# LED_Keychain_rev2.net
KiCad netlist of a schematic drawn in EAGLE
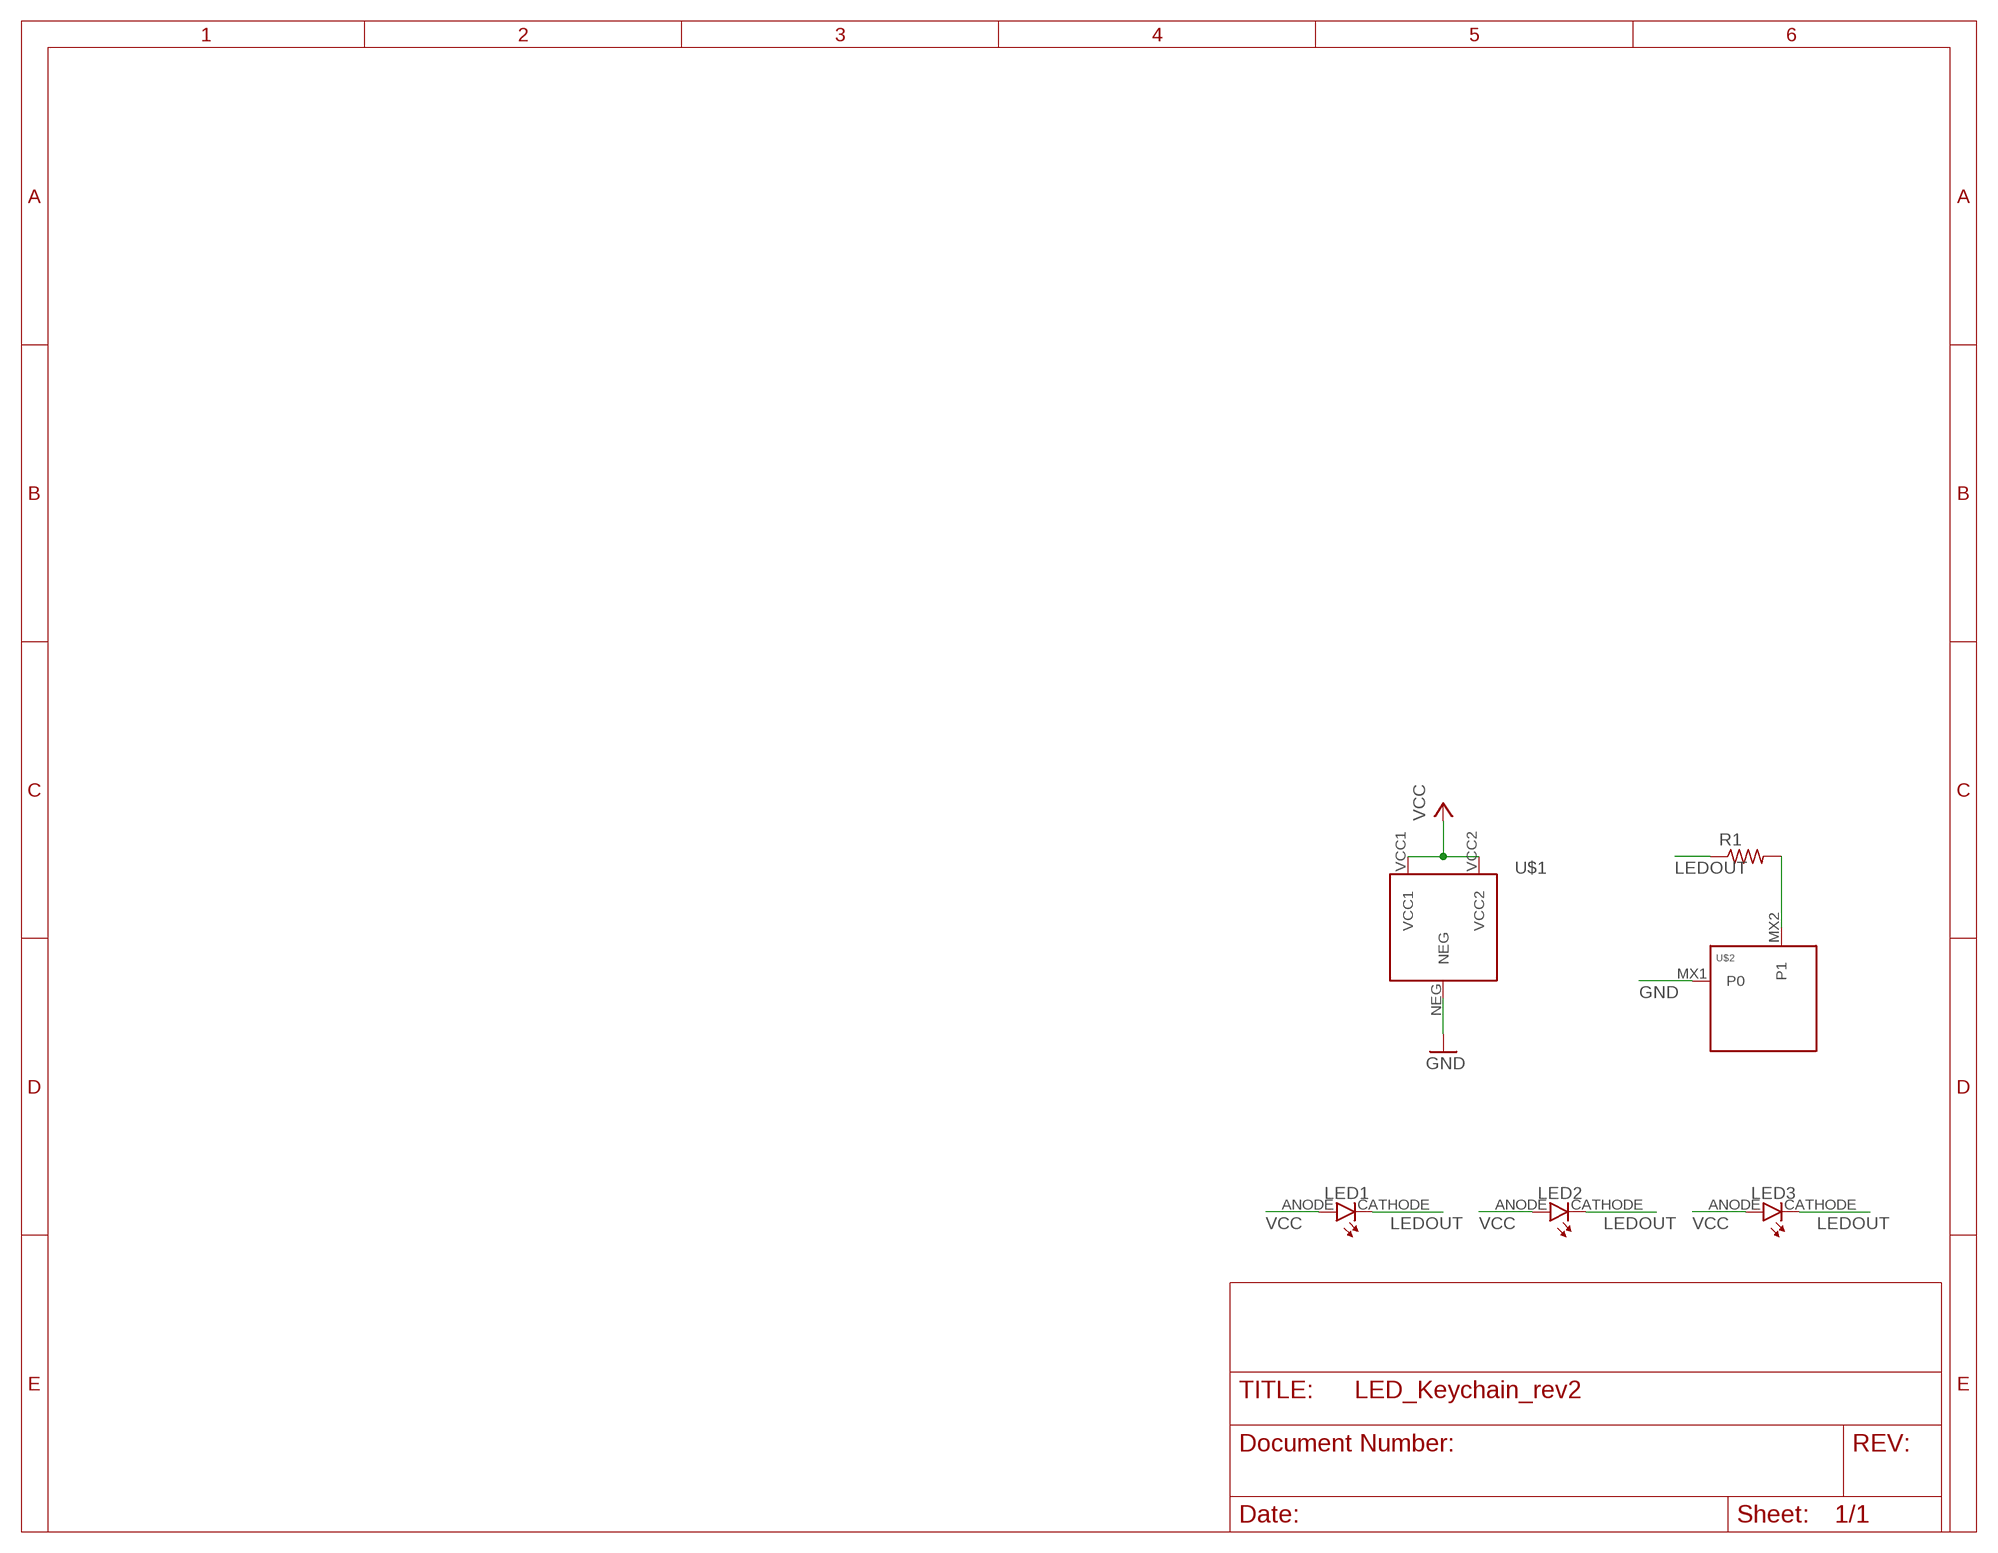
[diagram p0: schematic, sheet 1]

(export (version "E")
  (design (tool "Eeschema 10.0.6"))
  (components
    (comp (ref "LED1")
      (value "KINGBRIGHT-A1608")
      (footprint "eagle-import:KINGBRIGHT-0603")
      (libsource (lib "eagle-import") (part "KINGBRIGHT-A1608"))
    )
    (comp (ref "LED2")
      (value "KINGBRIGHT-A1608")
      (footprint "eagle-import:KINGBRIGHT-0603")
      (libsource (lib "eagle-import") (part "KINGBRIGHT-A1608"))
    )
    (comp (ref "LED3")
      (value "KINGBRIGHT-A1608")
      (footprint "eagle-import:KINGBRIGHT-0603")
      (libsource (lib "eagle-import") (part "KINGBRIGHT-A1608"))
    )
    (comp (ref "R1")
      (value "R-US_R0603")
      (footprint "eagle-import:R0603")
      (libsource (lib "eagle-import") (part "R-US_R0603"))
    )
    (comp (ref "U$1")
      (value "KEYSTONE3035")
      (footprint "eagle-import:KEYSTONE3035")
      (libsource (lib "eagle-import") (part "KEYSTONE3035"))
    )
    (comp (ref "U$2")
      (value "KEYSWITCH-PLAIN-MX-1U")
      (footprint "eagle-import:MX-1U")
      (libsource (lib "eagle-import") (part "KEYSWITCH-PLAIN-MX-1U"))
    )
  )
  (nets
    (net (code "1") (name "/LEDOUT") (class "Default")
      (node (ref "LED1") (pin "CATHODE") (pinfunction "CATHODE_CATHODE") (pintype "passive"))
      (node (ref "LED2") (pin "CATHODE") (pinfunction "CATHODE_CATHODE") (pintype "passive"))
      (node (ref "LED3") (pin "CATHODE") (pinfunction "CATHODE_CATHODE") (pintype "passive"))
      (node (ref "R1") (pin "1") (pinfunction "1_1") (pintype "passive"))
    )
    (net (code "2") (name "GND") (class "Default")
      (node (ref "U$1") (pin "NEG") (pinfunction "NEG_NEG") (pintype "bidirectional"))
      (node (ref "U$2") (pin "MX1") (pinfunction "P0_MX1") (pintype "bidirectional"))
    )
    (net (code "3") (name "Net-(U$2-P1)") (class "Default")
      (node (ref "R1") (pin "2") (pinfunction "2_2") (pintype "passive"))
      (node (ref "U$2") (pin "MX2") (pinfunction "P1_MX2") (pintype "bidirectional"))
    )
    (net (code "4") (name "VCC") (class "Default")
      (node (ref "LED1") (pin "ANODE") (pinfunction "ANODE_ANODE") (pintype "passive"))
      (node (ref "LED2") (pin "ANODE") (pinfunction "ANODE_ANODE") (pintype "passive"))
      (node (ref "LED3") (pin "ANODE") (pinfunction "ANODE_ANODE") (pintype "passive"))
      (node (ref "U$1") (pin "VCC1") (pinfunction "VCC1_VCC1") (pintype "bidirectional"))
      (node (ref "U$1") (pin "VCC2") (pinfunction "VCC2_VCC2") (pintype "bidirectional"))
    )
  )
)
